# Dormio.net
KiCad netlist of a schematic drawn in EAGLE
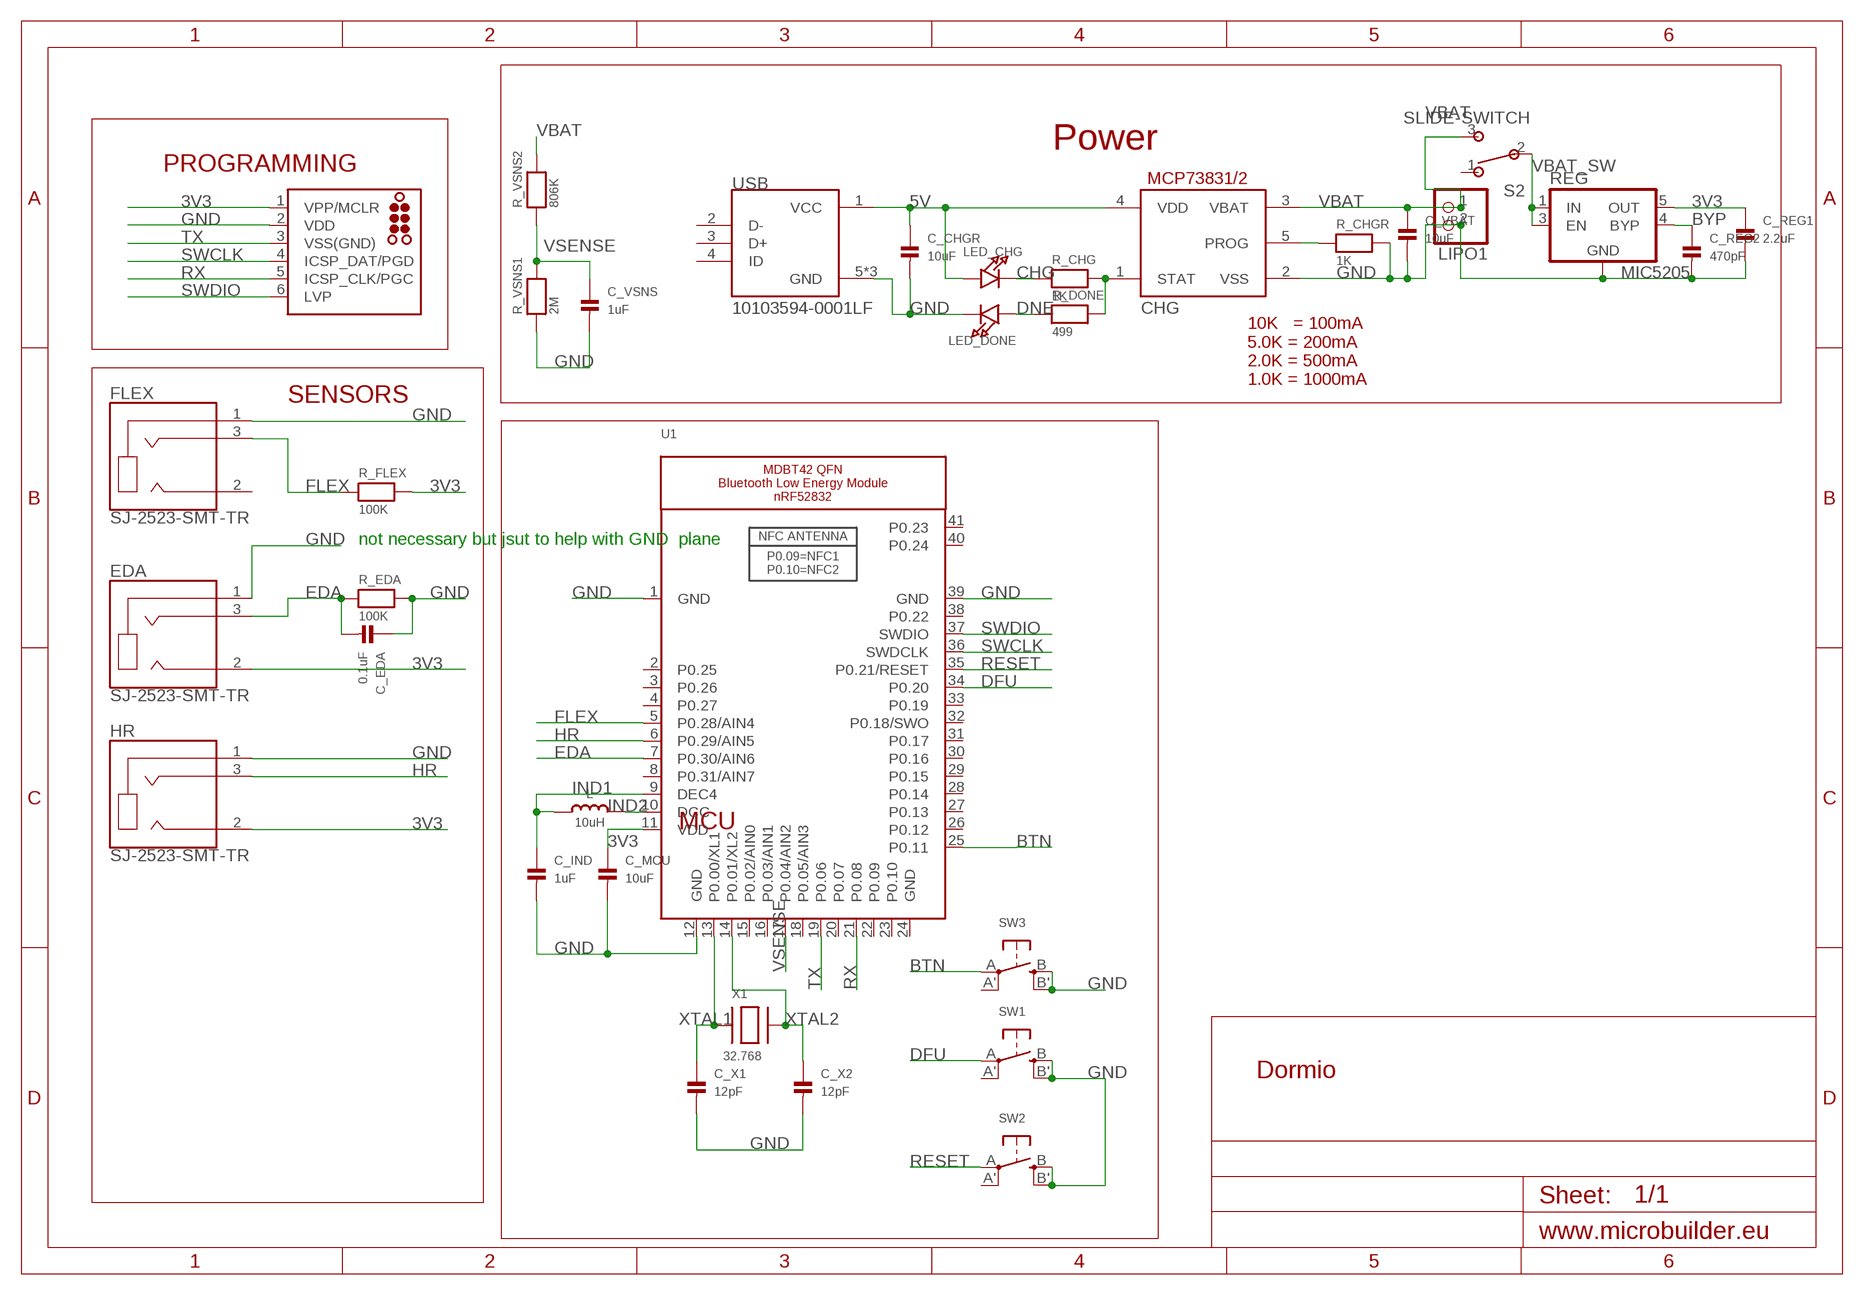
[diagram p0: schematic, sheet 1]

(export (version "E")
  (design (tool "Eeschema 10.0.6"))
  (components
    (comp (ref "CHG")
      (value "MCP73831/OT")
      (footprint "eagle-import:SOT23-5L")
      (libsource (lib "eagle-import") (part "MCP73831/OT"))
    )
    (comp (ref "C_CHGR")
      (value "10uF")
      (footprint "eagle-import:1206")
      (libsource (lib "eagle-import") (part "CAP_CERAMIC1206"))
    )
    (comp (ref "C_EDA")
      (value "0.1uF")
      (footprint "eagle-import:1206")
      (libsource (lib "eagle-import") (part "CAP_CERAMIC1206"))
    )
    (comp (ref "C_IND")
      (value "1uF")
      (footprint "eagle-import:1206")
      (libsource (lib "eagle-import") (part "CAP_CERAMIC1206"))
    )
    (comp (ref "C_MCU")
      (value "10uF")
      (footprint "eagle-import:1206")
      (libsource (lib "eagle-import") (part "CAP_CERAMIC1206"))
    )
    (comp (ref "C_REG1")
      (value "2.2uF")
      (footprint "eagle-import:1206")
      (libsource (lib "eagle-import") (part "CAP_CERAMIC1206"))
    )
    (comp (ref "C_REG2")
      (value "470pF")
      (footprint "eagle-import:1206")
      (libsource (lib "eagle-import") (part "CAP_CERAMIC1206"))
    )
    (comp (ref "C_VBAT")
      (value "10uF")
      (footprint "eagle-import:1206")
      (libsource (lib "eagle-import") (part "CAP_CERAMIC1206"))
    )
    (comp (ref "C_VSNS")
      (value "1uF")
      (footprint "eagle-import:1206")
      (libsource (lib "eagle-import") (part "CAP_CERAMIC1206"))
    )
    (comp (ref "C_X1")
      (value "12pF")
      (footprint "eagle-import:1206")
      (libsource (lib "eagle-import") (part "CAP_CERAMIC1206"))
    )
    (comp (ref "C_X2")
      (value "12pF")
      (footprint "eagle-import:1206")
      (libsource (lib "eagle-import") (part "CAP_CERAMIC1206"))
    )
    (comp (ref "EDA")
      (value "SJ-2523-SMT-TR")
      (footprint "eagle-import:CUI_SJ-2523-SMT-TR")
      (fields (field (name "MANUFACTURER") "CUI Inc."))
      (libsource (lib "eagle-import") (part "SJ-2523-SMT-TR"))
    )
    (comp (ref "FLEX")
      (value "SJ-2523-SMT-TR")
      (footprint "eagle-import:CUI_SJ-2523-SMT-TR")
      (fields (field (name "MANUFACTURER") "CUI Inc."))
      (libsource (lib "eagle-import") (part "SJ-2523-SMT-TR"))
    )
    (comp (ref "HR")
      (value "SJ-2523-SMT-TR")
      (footprint "eagle-import:CUI_SJ-2523-SMT-TR")
      (fields (field (name "MANUFACTURER") "CUI Inc."))
      (libsource (lib "eagle-import") (part "SJ-2523-SMT-TR"))
    )
    (comp (ref "J1")
      (value "TC2030-MCP-NL")
      (footprint "eagle-import:TC2030-MCP-NL")
      (libsource (lib "eagle-import") (part "TC2030-MCP-NL"))
    )
    (comp (ref "L")
      (value "10uH")
      (footprint "eagle-import:MICROBUILDER_INDUCTOR_1007")
      (libsource (lib "eagle-import") (part "MICROBUILDER_INDUCTOR"))
    )
    (comp (ref "LED_CHG")
      (value "LED1206")
      (footprint "eagle-import:CHIPLED_1206")
      (libsource (lib "eagle-import") (part "LED1206"))
    )
    (comp (ref "LED_DONE")
      (value "LED1206")
      (footprint "eagle-import:CHIPLED_1206")
      (libsource (lib "eagle-import") (part "LED1206"))
    )
    (comp (ref "LIPO1")
      (value "JST_2PIN-SMT-RA")
      (footprint "eagle-import:JST-PH-2-SMT-RA")
      (libsource (lib "eagle-import") (part "JST_2PIN-SMT-RA"))
    )
    (comp (ref "REG")
      (value "MIC5205")
      (footprint "eagle-import:SOT23-5")
      (libsource (lib "eagle-import") (part "MIC5205"))
    )
    (comp (ref "R_CHG")
      (value "1K")
      (footprint "eagle-import:1206")
      (libsource (lib "eagle-import") (part "RESISTOR1206"))
    )
    (comp (ref "R_CHGR")
      (value "1K")
      (footprint "eagle-import:1206")
      (libsource (lib "eagle-import") (part "RESISTOR1206"))
    )
    (comp (ref "R_DONE")
      (value "499")
      (footprint "eagle-import:1206")
      (libsource (lib "eagle-import") (part "RESISTOR1206"))
    )
    (comp (ref "R_EDA")
      (value "100K")
      (footprint "eagle-import:1206")
      (libsource (lib "eagle-import") (part "RESISTOR1206"))
    )
    (comp (ref "R_FLEX")
      (value "100K")
      (footprint "eagle-import:1206")
      (libsource (lib "eagle-import") (part "RESISTOR1206"))
    )
    (comp (ref "R_VSNS1")
      (value "2M")
      (footprint "eagle-import:1206")
      (libsource (lib "eagle-import") (part "RESISTOR1206"))
    )
    (comp (ref "R_VSNS2")
      (value "806K")
      (footprint "eagle-import:1206")
      (libsource (lib "eagle-import") (part "RESISTOR1206"))
    )
    (comp (ref "S2")
      (value "SLIDE-SWITCH")
      (footprint "eagle-import:AYZ0102AGRLC")
      (libsource (lib "eagle-import") (part "SLIDE-SWITCH"))
    )
    (comp (ref "SW1")
      (value "MICROBUILDER_SWITCH_TACT_SMT4.6X2.8")
      (footprint "eagle-import:MICROBUILDER_BTN_KMR2_4.6X2.8")
      (libsource (lib "eagle-import") (part "MICROBUILDER_SWITCH_TACT_SMT4.6X2.8"))
    )
    (comp (ref "SW2")
      (value "MICROBUILDER_SWITCH_TACT_SMT4.6X2.8")
      (footprint "eagle-import:MICROBUILDER_BTN_KMR2_4.6X2.8")
      (libsource (lib "eagle-import") (part "MICROBUILDER_SWITCH_TACT_SMT4.6X2.8"))
    )
    (comp (ref "SW3")
      (value "MICROBUILDER_SWITCH_TACT_SMT4.6X2.8")
      (footprint "eagle-import:MICROBUILDER_BTN_KMR2_4.6X2.8")
      (libsource (lib "eagle-import") (part "MICROBUILDER_SWITCH_TACT_SMT4.6X2.8"))
    )
    (comp (ref "U1")
      (value "MICROBUILDER_NRF52832_MODULE_MDBT42")
      (footprint "eagle-import:MICROBUILDER_BLE_MODULE_RAYTAC_MDBT42")
      (fields (field (name "SPICEPREFIX") "X"))
      (libsource (lib "eagle-import") (part "MICROBUILDER_NRF52832_MODULE_MDBT42"))
    )
    (comp (ref "USB")
      (value "10103594-0001LF")
      (footprint "eagle-import:FCI_10103594-0001LF")
      (fields (field (name "MF") "FCI"))
      (libsource (lib "eagle-import") (part "10103594-0001LF"))
    )
    (comp (ref "X1")
      (value "32.768")
      (footprint "eagle-import:XTAL3215")
      (libsource (lib "eagle-import") (part "XTAL-3.2X1.5"))
    )
  )
  (nets
    (net (code "1") (name "/3V3") (class "Default")
      (node (ref "C_MCU") (pin "1") (pinfunction "P$1_1") (pintype "passive"))
      (node (ref "C_REG1") (pin "1") (pinfunction "P$1_1") (pintype "passive"))
      (node (ref "EDA") (pin "2") (pinfunction "2_2") (pintype "passive"))
      (node (ref "HR") (pin "2") (pinfunction "2_2") (pintype "passive"))
      (node (ref "J1") (pin "1") (pinfunction "VPP/MCLR_1") (pintype "passive"))
      (node (ref "REG") (pin "5") (pinfunction "OUT_5") (pintype "power_in"))
      (node (ref "R_FLEX") (pin "2") (pinfunction "2_2") (pintype "passive"))
      (node (ref "U1") (pin "11") (pinfunction "VDD_11") (pintype "bidirectional"))
    )
    (net (code "2") (name "/5V") (class "Default")
      (node (ref "CHG") (pin "4") (pinfunction "VDD_4") (pintype "power_in"))
      (node (ref "C_CHGR") (pin "1") (pinfunction "P$1_1") (pintype "passive"))
      (node (ref "LED_CHG") (pin "A") (pinfunction "A_A") (pintype "passive"))
      (node (ref "USB") (pin "1") (pinfunction "VCC_1") (pintype "power_in"))
    )
    (net (code "3") (name "/BTN") (class "Default")
      (node (ref "SW3") (pin "A") (pinfunction "P_A") (pintype "passive"))
      (node (ref "U1") (pin "25") (pinfunction "P0.11_25") (pintype "bidirectional"))
    )
    (net (code "4") (name "/BYP") (class "Default")
      (node (ref "C_REG2") (pin "1") (pinfunction "P$1_1") (pintype "passive"))
      (node (ref "REG") (pin "4") (pinfunction "BYP_4") (pintype "bidirectional"))
    )
    (net (code "5") (name "/CHG") (class "Default")
      (node (ref "LED_CHG") (pin "C") (pinfunction "C_C") (pintype "passive"))
      (node (ref "R_CHG") (pin "1") (pinfunction "1_1") (pintype "passive"))
    )
    (net (code "6") (name "/DFU") (class "Default")
      (node (ref "SW1") (pin "A") (pinfunction "P_A") (pintype "passive"))
      (node (ref "U1") (pin "34") (pinfunction "P0.20_34") (pintype "bidirectional"))
    )
    (net (code "7") (name "/DNE") (class "Default")
      (node (ref "LED_DONE") (pin "A") (pinfunction "A_A") (pintype "passive"))
      (node (ref "R_DONE") (pin "1") (pinfunction "1_1") (pintype "passive"))
    )
    (net (code "8") (name "/EDA") (class "Default")
      (node (ref "C_EDA") (pin "2") (pinfunction "P$2_2") (pintype "passive"))
      (node (ref "EDA") (pin "3") (pinfunction "3_3") (pintype "passive"))
      (node (ref "R_EDA") (pin "1") (pinfunction "1_1") (pintype "passive"))
      (node (ref "U1") (pin "7") (pinfunction "P0.30/AIN6_7") (pintype "bidirectional"))
    )
    (net (code "9") (name "/FLEX") (class "Default")
      (node (ref "FLEX") (pin "3") (pinfunction "3_3") (pintype "passive"))
      (node (ref "R_FLEX") (pin "1") (pinfunction "1_1") (pintype "passive"))
      (node (ref "U1") (pin "5") (pinfunction "P0.28/AIN4_5") (pintype "bidirectional"))
    )
    (net (code "10") (name "/GND") (class "Default")
      (node (ref "CHG") (pin "2") (pinfunction "VSS_2") (pintype "power_in"))
      (node (ref "C_CHGR") (pin "2") (pinfunction "P$2_2") (pintype "passive"))
      (node (ref "C_EDA") (pin "1") (pinfunction "P$1_1") (pintype "passive"))
      (node (ref "C_IND") (pin "2") (pinfunction "P$2_2") (pintype "passive"))
      (node (ref "C_MCU") (pin "2") (pinfunction "P$2_2") (pintype "passive"))
      (node (ref "C_REG1") (pin "2") (pinfunction "P$2_2") (pintype "passive"))
      (node (ref "C_REG2") (pin "2") (pinfunction "P$2_2") (pintype "passive"))
      (node (ref "C_VBAT") (pin "2") (pinfunction "P$2_2") (pintype "passive"))
      (node (ref "C_VSNS") (pin "2") (pinfunction "P$2_2") (pintype "passive"))
      (node (ref "C_X1") (pin "2") (pinfunction "P$2_2") (pintype "passive"))
      (node (ref "C_X2") (pin "2") (pinfunction "P$2_2") (pintype "passive"))
      (node (ref "EDA") (pin "1") (pinfunction "1_1") (pintype "passive"))
      (node (ref "FLEX") (pin "1") (pinfunction "1_1") (pintype "passive"))
      (node (ref "HR") (pin "1") (pinfunction "1_1") (pintype "passive"))
      (node (ref "J1") (pin "2") (pinfunction "VDD_2") (pintype "power_in"))
      (node (ref "LED_DONE") (pin "C") (pinfunction "C_C") (pintype "passive"))
      (node (ref "LIPO1") (pin "2") (pinfunction "1_2") (pintype "passive"))
      (node (ref "REG") (pin "2") (pinfunction "GND_2") (pintype "power_in"))
      (node (ref "R_CHGR") (pin "2") (pinfunction "2_2") (pintype "passive"))
      (node (ref "R_EDA") (pin "2") (pinfunction "2_2") (pintype "passive"))
      (node (ref "R_VSNS1") (pin "1") (pinfunction "1_1") (pintype "passive"))
      (node (ref "SW1") (pin "B") (pinfunction "S_B") (pintype "passive"))
      (node (ref "SW1") (pin "B'") (pinfunction "S1_B'") (pintype "passive"))
      (node (ref "SW2") (pin "B") (pinfunction "S_B") (pintype "passive"))
      (node (ref "SW2") (pin "B'") (pinfunction "S1_B'") (pintype "passive"))
      (node (ref "SW3") (pin "B") (pinfunction "S_B") (pintype "passive"))
      (node (ref "SW3") (pin "B'") (pinfunction "S1_B'") (pintype "passive"))
      (node (ref "U1") (pin "1") (pinfunction "GND_1") (pintype "bidirectional"))
      (node (ref "U1") (pin "12") (pinfunction "GND_12") (pintype "bidirectional"))
      (node (ref "U1") (pin "39") (pinfunction "GND_39") (pintype "bidirectional"))
      (node (ref "USB") (pin "5") (pinfunction "GND_5") (pintype "power_in"))
      (node (ref "USB") (pin "P3") (pinfunction "GND_P3") (pintype "power_in"))
      (node (ref "USB") (pin "P4") (pinfunction "GND_P4") (pintype "power_in"))
    )
    (net (code "11") (name "/HR") (class "Default")
      (node (ref "HR") (pin "3") (pinfunction "3_3") (pintype "passive"))
      (node (ref "U1") (pin "6") (pinfunction "P0.29/AIN5_6") (pintype "bidirectional"))
    )
    (net (code "12") (name "/IND1") (class "Default")
      (node (ref "C_IND") (pin "1") (pinfunction "P$1_1") (pintype "passive"))
      (node (ref "L") (pin "P$1") (pinfunction "1_P$1") (pintype "passive"))
      (node (ref "U1") (pin "9") (pinfunction "DEC4_9") (pintype "bidirectional"))
    )
    (net (code "13") (name "/IND2") (class "Default")
      (node (ref "L") (pin "P$2") (pinfunction "2_P$2") (pintype "passive"))
      (node (ref "U1") (pin "10") (pinfunction "DCC_10") (pintype "bidirectional"))
    )
    (net (code "14") (name "/RESET") (class "Default")
      (node (ref "SW2") (pin "A") (pinfunction "P_A") (pintype "passive"))
      (node (ref "U1") (pin "35") (pinfunction "P0.21/RESET_35") (pintype "bidirectional"))
    )
    (net (code "15") (name "/RX") (class "Default")
      (node (ref "J1") (pin "5") (pinfunction "ICSP_CLK/PGC_5") (pintype "output"))
      (node (ref "U1") (pin "21") (pinfunction "P0.08_21") (pintype "bidirectional"))
    )
    (net (code "16") (name "/SWCLK") (class "Default")
      (node (ref "J1") (pin "4") (pinfunction "ICSP_DAT/PGD_4") (pintype "bidirectional"))
      (node (ref "U1") (pin "36") (pinfunction "SWDCLK_36") (pintype "bidirectional"))
    )
    (net (code "17") (name "/SWDIO") (class "Default")
      (node (ref "J1") (pin "6") (pinfunction "LVP_6") (pintype "bidirectional"))
      (node (ref "U1") (pin "37") (pinfunction "SWDIO_37") (pintype "bidirectional"))
    )
    (net (code "18") (name "/TX") (class "Default")
      (node (ref "J1") (pin "3") (pinfunction "VSS(GND)_3") (pintype "power_in"))
      (node (ref "U1") (pin "19") (pinfunction "P0.06_19") (pintype "bidirectional"))
    )
    (net (code "19") (name "/VBAT") (class "Default")
      (node (ref "CHG") (pin "3") (pinfunction "VBAT_3") (pintype "bidirectional"))
      (node (ref "C_VBAT") (pin "1") (pinfunction "P$1_1") (pintype "passive"))
      (node (ref "LIPO1") (pin "1") (pinfunction "2_1") (pintype "passive"))
      (node (ref "R_VSNS2") (pin "2") (pinfunction "2_2") (pintype "passive"))
      (node (ref "S2") (pin "3") (pinfunction "3_3") (pintype "bidirectional"))
    )
    (net (code "20") (name "/VBAT_SW") (class "Default")
      (node (ref "REG") (pin "1") (pinfunction "IN_1") (pintype "power_in"))
      (node (ref "REG") (pin "3") (pinfunction "EN_3") (pintype "input"))
      (node (ref "S2") (pin "2") (pinfunction "2_2") (pintype "bidirectional"))
    )
    (net (code "21") (name "/VSENSE") (class "Default")
      (node (ref "C_VSNS") (pin "1") (pinfunction "P$1_1") (pintype "passive"))
      (node (ref "R_VSNS1") (pin "2") (pinfunction "2_2") (pintype "passive"))
      (node (ref "R_VSNS2") (pin "1") (pinfunction "1_1") (pintype "passive"))
      (node (ref "U1") (pin "17") (pinfunction "P0.04/AIN2_17") (pintype "bidirectional"))
    )
    (net (code "22") (name "/XTAL1") (class "Default")
      (node (ref "C_X1") (pin "1") (pinfunction "P$1_1") (pintype "passive"))
      (node (ref "U1") (pin "13") (pinfunction "P0.00/XL1_13") (pintype "bidirectional"))
      (node (ref "X1") (pin "P$1") (pinfunction "P$1_P$1") (pintype "bidirectional"))
    )
    (net (code "23") (name "/XTAL2") (class "Default")
      (node (ref "C_X2") (pin "1") (pinfunction "P$1_1") (pintype "passive"))
      (node (ref "U1") (pin "14") (pinfunction "P0.01/XL2_14") (pintype "bidirectional"))
      (node (ref "X1") (pin "P$2") (pinfunction "P$2_P$2") (pintype "bidirectional"))
    )
    (net (code "24") (name "Net-(CHG-PROG)") (class "Default")
      (node (ref "CHG") (pin "5") (pinfunction "PROG_5") (pintype "input"))
      (node (ref "R_CHGR") (pin "1") (pinfunction "1_1") (pintype "passive"))
    )
    (net (code "25") (name "Net-(CHG-STAT)") (class "Default")
      (node (ref "CHG") (pin "1") (pinfunction "STAT_1") (pintype "output"))
      (node (ref "R_CHG") (pin "2") (pinfunction "2_2") (pintype "passive"))
      (node (ref "R_DONE") (pin "2") (pinfunction "2_2") (pintype "passive"))
    )
    (net (code "26") (name "unconnected-(FLEX-Pad2)") (class "Default")
      (node (ref "FLEX") (pin "2") (pinfunction "2_2") (pintype "passive"))
    )
    (net (code "27") (name "unconnected-(S2-Pad1)") (class "Default")
      (node (ref "S2") (pin "1") (pinfunction "1_1") (pintype "bidirectional"))
    )
    (net (code "28") (name "unconnected-(SW1-P1-PadA')") (class "Default")
      (node (ref "SW1") (pin "A'") (pinfunction "P1_A'") (pintype "passive"))
    )
    (net (code "29") (name "unconnected-(SW2-P1-PadA')") (class "Default")
      (node (ref "SW2") (pin "A'") (pinfunction "P1_A'") (pintype "passive"))
    )
    (net (code "30") (name "unconnected-(SW3-P1-PadA')") (class "Default")
      (node (ref "SW3") (pin "A'") (pinfunction "P1_A'") (pintype "passive"))
    )
    (net (code "31") (name "unconnected-(U1-GND-Pad24)") (class "Default")
      (node (ref "U1") (pin "24") (pinfunction "GND_24") (pintype "bidirectional"))
    )
    (net (code "32") (name "unconnected-(U1-P0.02{slash}AIN0-Pad15)") (class "Default")
      (node (ref "U1") (pin "15") (pinfunction "P0.02/AIN0_15") (pintype "bidirectional"))
    )
    (net (code "33") (name "unconnected-(U1-P0.03{slash}AIN1-Pad16)") (class "Default")
      (node (ref "U1") (pin "16") (pinfunction "P0.03/AIN1_16") (pintype "bidirectional"))
    )
    (net (code "34") (name "unconnected-(U1-P0.05{slash}AIN3-Pad18)") (class "Default")
      (node (ref "U1") (pin "18") (pinfunction "P0.05/AIN3_18") (pintype "bidirectional"))
    )
    (net (code "35") (name "unconnected-(U1-P0.07-Pad20)") (class "Default")
      (node (ref "U1") (pin "20") (pinfunction "P0.07_20") (pintype "bidirectional"))
    )
    (net (code "36") (name "unconnected-(U1-P0.09-Pad22)") (class "Default")
      (node (ref "U1") (pin "22") (pinfunction "P0.09_22") (pintype "bidirectional"))
    )
    (net (code "37") (name "unconnected-(U1-P0.10-Pad23)") (class "Default")
      (node (ref "U1") (pin "23") (pinfunction "P0.10_23") (pintype "bidirectional"))
    )
    (net (code "38") (name "unconnected-(U1-P0.12-Pad26)") (class "Default")
      (node (ref "U1") (pin "26") (pinfunction "P0.12_26") (pintype "bidirectional"))
    )
    (net (code "39") (name "unconnected-(U1-P0.13-Pad27)") (class "Default")
      (node (ref "U1") (pin "27") (pinfunction "P0.13_27") (pintype "bidirectional"))
    )
    (net (code "40") (name "unconnected-(U1-P0.14-Pad28)") (class "Default")
      (node (ref "U1") (pin "28") (pinfunction "P0.14_28") (pintype "bidirectional"))
    )
    (net (code "41") (name "unconnected-(U1-P0.15-Pad29)") (class "Default")
      (node (ref "U1") (pin "29") (pinfunction "P0.15_29") (pintype "bidirectional"))
    )
    (net (code "42") (name "unconnected-(U1-P0.16-Pad30)") (class "Default")
      (node (ref "U1") (pin "30") (pinfunction "P0.16_30") (pintype "bidirectional"))
    )
    (net (code "43") (name "unconnected-(U1-P0.17-Pad31)") (class "Default")
      (node (ref "U1") (pin "31") (pinfunction "P0.17_31") (pintype "bidirectional"))
    )
    (net (code "44") (name "unconnected-(U1-P0.18{slash}SWO-Pad32)") (class "Default")
      (node (ref "U1") (pin "32") (pinfunction "P0.18/SWO_32") (pintype "bidirectional"))
    )
    (net (code "45") (name "unconnected-(U1-P0.19-Pad33)") (class "Default")
      (node (ref "U1") (pin "33") (pinfunction "P0.19_33") (pintype "bidirectional"))
    )
    (net (code "46") (name "unconnected-(U1-P0.22-Pad38)") (class "Default")
      (node (ref "U1") (pin "38") (pinfunction "P0.22_38") (pintype "bidirectional"))
    )
    (net (code "47") (name "unconnected-(U1-P0.23-Pad41)") (class "Default")
      (node (ref "U1") (pin "41") (pinfunction "P0.23_41") (pintype "bidirectional"))
    )
    (net (code "48") (name "unconnected-(U1-P0.24-Pad40)") (class "Default")
      (node (ref "U1") (pin "40") (pinfunction "P0.24_40") (pintype "bidirectional"))
    )
    (net (code "49") (name "unconnected-(U1-P0.25-Pad2)") (class "Default")
      (node (ref "U1") (pin "2") (pinfunction "P0.25_2") (pintype "bidirectional"))
    )
    (net (code "50") (name "unconnected-(U1-P0.26-Pad3)") (class "Default")
      (node (ref "U1") (pin "3") (pinfunction "P0.26_3") (pintype "bidirectional"))
    )
    (net (code "51") (name "unconnected-(U1-P0.27-Pad4)") (class "Default")
      (node (ref "U1") (pin "4") (pinfunction "P0.27_4") (pintype "bidirectional"))
    )
    (net (code "52") (name "unconnected-(U1-P0.31{slash}AIN7-Pad8)") (class "Default")
      (node (ref "U1") (pin "8") (pinfunction "P0.31/AIN7_8") (pintype "bidirectional"))
    )
    (net (code "53") (name "unconnected-(USB-D+-Pad3)") (class "Default")
      (node (ref "USB") (pin "3") (pinfunction "D+_3") (pintype "bidirectional"))
    )
    (net (code "54") (name "unconnected-(USB-D--Pad2)") (class "Default")
      (node (ref "USB") (pin "2") (pinfunction "D-_2") (pintype "bidirectional"))
    )
    (net (code "55") (name "unconnected-(USB-ID-Pad4)") (class "Default")
      (node (ref "USB") (pin "4") (pinfunction "ID_4") (pintype "bidirectional"))
    )
  )
)
